# Controler_3_5.net
KiCad netlist of a schematic drawn in EAGLE
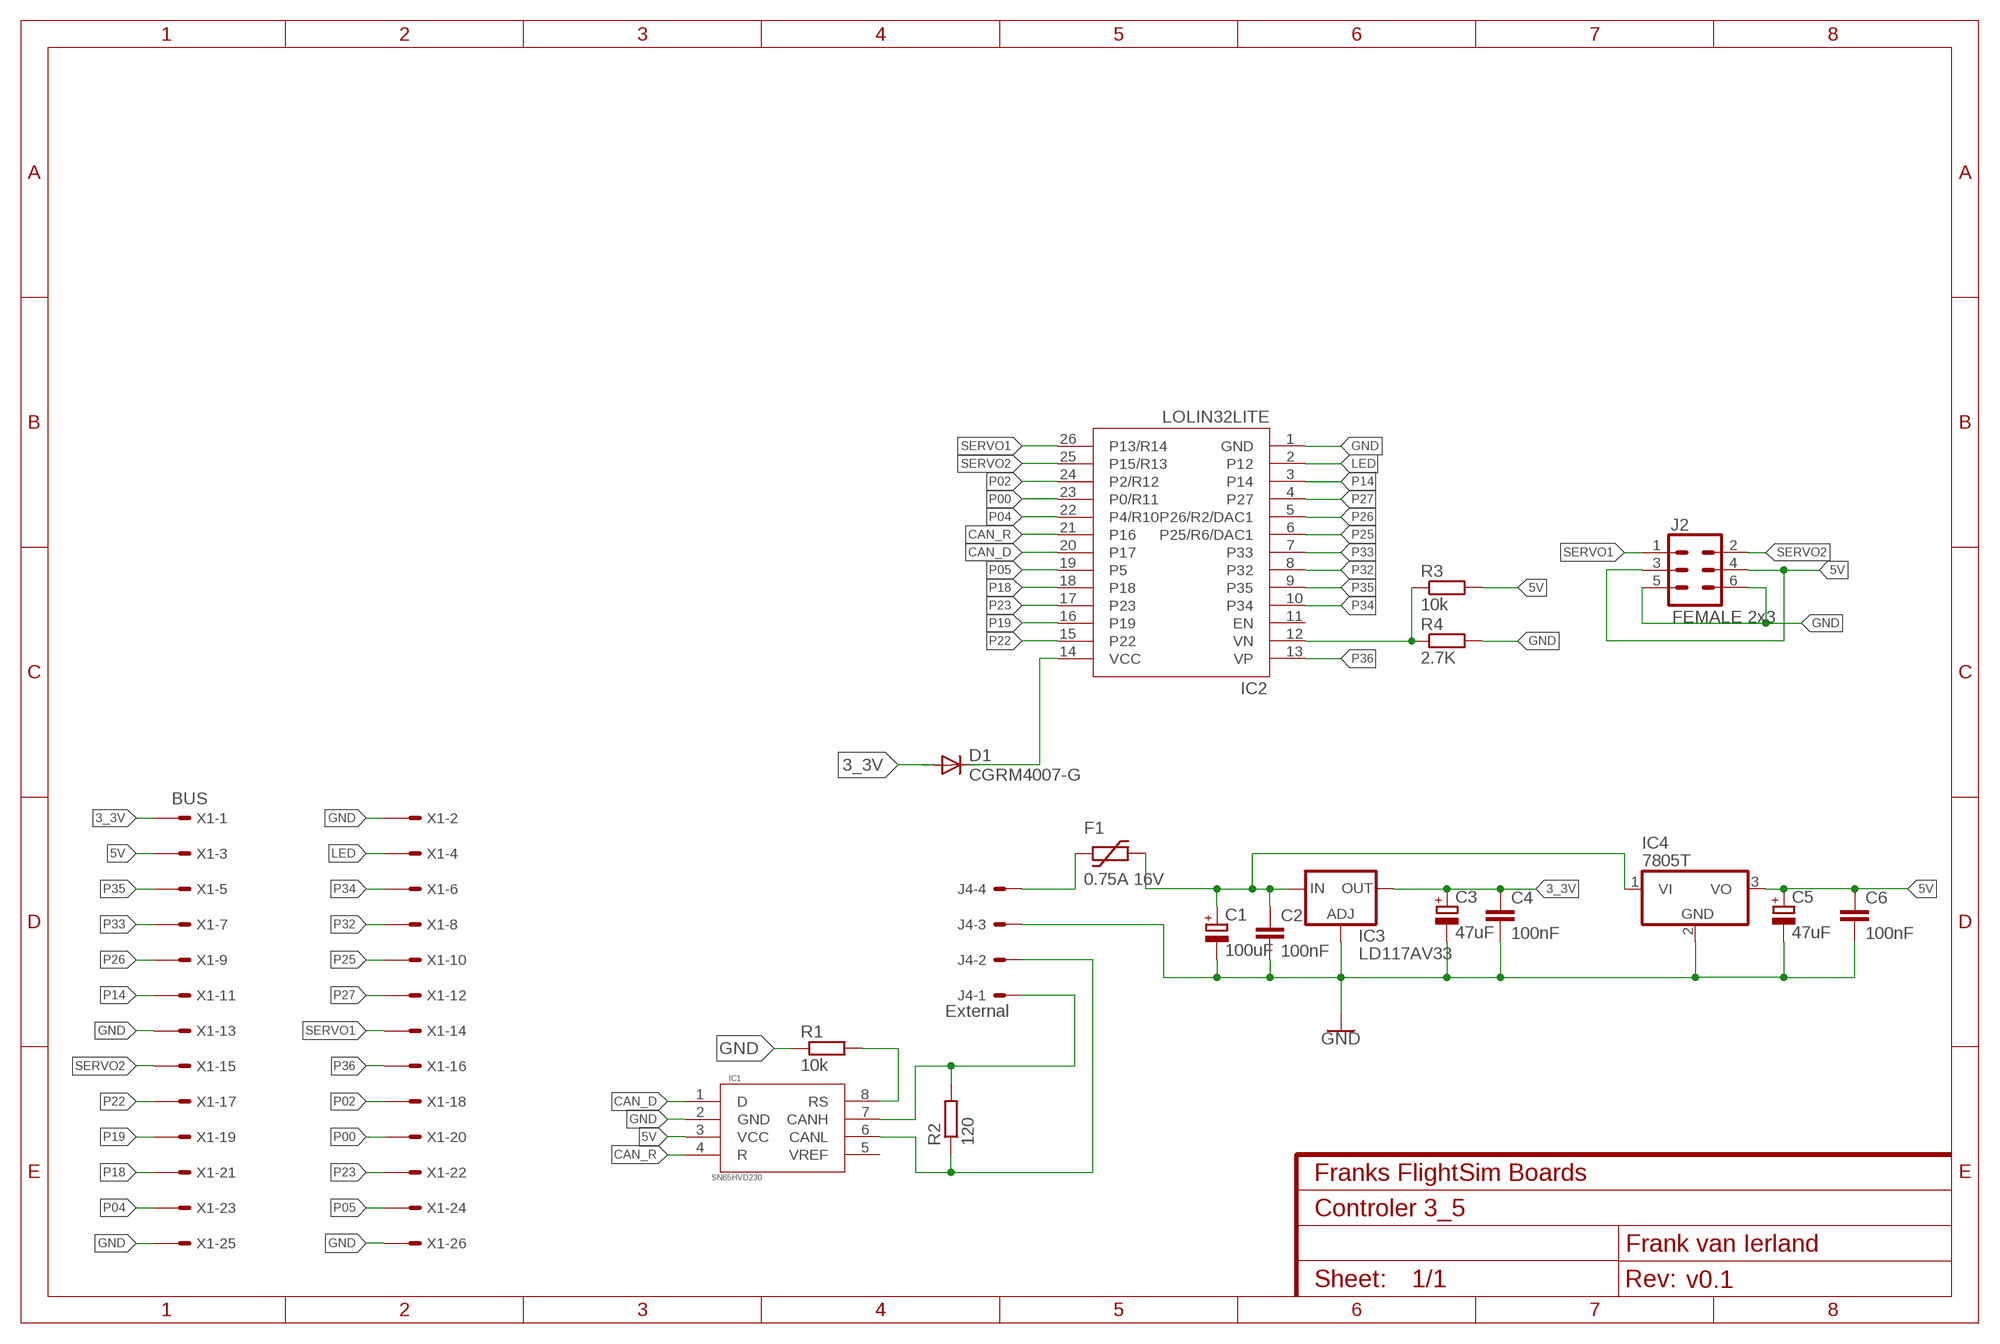
[diagram p0: schematic, sheet 1]

(export (version "E")
  (design (tool "Eeschema 10.0.6"))
  (components
    (comp (ref "C1")
      (value "100uF")
      (footprint "eagle-import:153CLV-0505")
      (libsource (lib "eagle-import") (part "CPOL-EU153CLV-0505"))
    )
    (comp (ref "C2")
      (value "100nF")
      (footprint "eagle-import:C0805")
      (libsource (lib "eagle-import") (part "C-EUC0805"))
    )
    (comp (ref "C3")
      (value "47uF")
      (footprint "eagle-import:CT3528")
      (libsource (lib "eagle-import") (part "CPOL-EUCT3528"))
    )
    (comp (ref "C4")
      (value "100nF")
      (footprint "eagle-import:C0805")
      (libsource (lib "eagle-import") (part "C-EUC0805"))
    )
    (comp (ref "C5")
      (value "47uF")
      (footprint "eagle-import:CT3528")
      (libsource (lib "eagle-import") (part "CPOL-EUCT3528"))
    )
    (comp (ref "C6")
      (value "100nF")
      (footprint "eagle-import:C0805")
      (libsource (lib "eagle-import") (part "C-EUC0805"))
    )
    (comp (ref "D1")
      (value "CGRM4007-G")
      (footprint "eagle-import:SOD-123_MINI-SMA")
      (libsource (lib "eagle-import") (part "CGRM400-G7"))
    )
    (comp (ref "F1")
      (value "0.75A 16V")
      (footprint "eagle-import:1812L")
      (libsource (lib "eagle-import") (part "1812L"))
    )
    (comp (ref "IC1")
      (value "SN65HVD230")
      (footprint "eagle-import:SO08")
      (libsource (lib "eagle-import") (part "SN65HVD230"))
    )
    (comp (ref "IC2")
      (value "LOLIN32LITE")
      (footprint "eagle-import:LOLIN32LITE")
      (libsource (lib "eagle-import") (part "LOLIN32LITE"))
    )
    (comp (ref "IC3")
      (value "LD117AV33")
      (footprint "eagle-import:TO220L1")
      (libsource (lib "eagle-import") (part "LD117A?V33"))
    )
    (comp (ref "IC4")
      (value "7805T")
      (footprint "eagle-import:TO220H")
      (libsource (lib "eagle-import") (part "78T05"))
    )
    (comp (ref "J2")
      (value "FEMALE 2x3")
      (footprint "eagle-import:2X3")
      (libsource (lib "eagle-import") (part "CONN_03X2FEMALE"))
    )
    (comp (ref "J4")
      (value "External")
      (footprint "eagle-import:6410-04")
      (fields (field (name "MF") "MOLEX"))
      (libsource (lib "eagle-import") (part "22-?-0427-2041"))
    )
    (comp (ref "R1")
      (value "10k")
      (footprint "eagle-import:M1206")
      (libsource (lib "eagle-import") (part "R-EU_M1206"))
    )
    (comp (ref "R2")
      (value "120")
      (footprint "eagle-import:R1210")
      (libsource (lib "eagle-import") (part "R-EU_R1210"))
    )
    (comp (ref "R3")
      (value "10k")
      (footprint "eagle-import:M1206")
      (libsource (lib "eagle-import") (part "R-EU_M1206"))
    )
    (comp (ref "R4")
      (value "2.7K")
      (footprint "eagle-import:M1206")
      (libsource (lib "eagle-import") (part "R-EU_M1206"))
    )
    (comp (ref "X1")
      (value "BUS")
      (footprint "eagle-import:057-026-1")
      (libsource (lib "eagle-import") (part "057-026-1"))
    )
  )
  (nets
    (net (code "1") (name "3_3V") (class "Default")
      (node (ref "C3") (pin "+") (pinfunction "+_+") (pintype "passive"))
      (node (ref "C4") (pin "1") (pinfunction "1_1") (pintype "passive"))
      (node (ref "D1") (pin "A") (pinfunction "A_A") (pintype "passive"))
      (node (ref "IC3") (pin "2") (pinfunction "OUT_2") (pintype "passive"))
      (node (ref "X1") (pin "1") (pinfunction "S_1") (pintype "passive"))
    )
    (net (code "2") (name "5V") (class "Default")
      (node (ref "C5") (pin "+") (pinfunction "+_+") (pintype "passive"))
      (node (ref "C6") (pin "1") (pinfunction "1_1") (pintype "passive"))
      (node (ref "IC1") (pin "3") (pinfunction "VCC_3") (pintype "bidirectional"))
      (node (ref "IC4") (pin "3") (pinfunction "VO_3") (pintype "passive"))
      (node (ref "J2") (pin "3") (pinfunction "3_3") (pintype "bidirectional"))
      (node (ref "J2") (pin "4") (pinfunction "4_4") (pintype "bidirectional"))
      (node (ref "R3") (pin "2") (pinfunction "2_2") (pintype "passive"))
      (node (ref "X1") (pin "3") (pinfunction "S_3") (pintype "passive"))
    )
    (net (code "3") (name "CAN_D") (class "Default")
      (node (ref "IC1") (pin "1") (pinfunction "D_1") (pintype "bidirectional"))
      (node (ref "IC2") (pin "20") (pinfunction "P17_20") (pintype "bidirectional"))
    )
    (net (code "4") (name "CAN_R") (class "Default")
      (node (ref "IC1") (pin "4") (pinfunction "R_4") (pintype "bidirectional"))
      (node (ref "IC2") (pin "21") (pinfunction "P16_21") (pintype "bidirectional"))
    )
    (net (code "5") (name "GND") (class "Default")
      (node (ref "C1") (pin "-") (pinfunction "-_-") (pintype "passive"))
      (node (ref "C2") (pin "2") (pinfunction "2_2") (pintype "passive"))
      (node (ref "C3") (pin "-") (pinfunction "-_-") (pintype "passive"))
      (node (ref "C4") (pin "2") (pinfunction "2_2") (pintype "passive"))
      (node (ref "C5") (pin "-") (pinfunction "-_-") (pintype "passive"))
      (node (ref "C6") (pin "2") (pinfunction "2_2") (pintype "passive"))
      (node (ref "IC1") (pin "2") (pinfunction "GND_2") (pintype "bidirectional"))
      (node (ref "IC2") (pin "1") (pinfunction "GND_1") (pintype "power_in"))
      (node (ref "IC3") (pin "1") (pinfunction "ADJ_1") (pintype "input"))
      (node (ref "IC4") (pin "2") (pinfunction "GND_2") (pintype "passive"))
      (node (ref "J2") (pin "5") (pinfunction "5_5") (pintype "bidirectional"))
      (node (ref "J2") (pin "6") (pinfunction "6_6") (pintype "bidirectional"))
      (node (ref "J4") (pin "3") (pinfunction "S_3") (pintype "passive"))
      (node (ref "R1") (pin "1") (pinfunction "1_1") (pintype "passive"))
      (node (ref "R4") (pin "2") (pinfunction "2_2") (pintype "passive"))
      (node (ref "X1") (pin "13") (pinfunction "S_13") (pintype "passive"))
      (node (ref "X1") (pin "2") (pinfunction "S_2") (pintype "passive"))
      (node (ref "X1") (pin "25") (pinfunction "S_25") (pintype "passive"))
      (node (ref "X1") (pin "26") (pinfunction "S_26") (pintype "passive"))
    )
    (net (code "6") (name "LED") (class "Default")
      (node (ref "IC2") (pin "2") (pinfunction "P12_2") (pintype "bidirectional"))
      (node (ref "X1") (pin "4") (pinfunction "S_4") (pintype "passive"))
    )
    (net (code "7") (name "Net-(IC1-CANH)") (class "Default")
      (node (ref "IC1") (pin "7") (pinfunction "CANH_7") (pintype "bidirectional"))
      (node (ref "J4") (pin "1") (pinfunction "S_1") (pintype "passive"))
      (node (ref "R2") (pin "2") (pinfunction "2_2") (pintype "passive"))
    )
    (net (code "8") (name "Net-(IC1-CANL)") (class "Default")
      (node (ref "IC1") (pin "6") (pinfunction "CANL_6") (pintype "bidirectional"))
      (node (ref "J4") (pin "2") (pinfunction "S_2") (pintype "passive"))
      (node (ref "R2") (pin "1") (pinfunction "1_1") (pintype "passive"))
    )
    (net (code "9") (name "Net-(IC1-RS)") (class "Default")
      (node (ref "IC1") (pin "8") (pinfunction "RS_8") (pintype "bidirectional"))
      (node (ref "R1") (pin "2") (pinfunction "2_2") (pintype "passive"))
    )
    (net (code "10") (name "Net-(IC2-VCC)") (class "Default")
      (node (ref "D1") (pin "C") (pinfunction "C_C") (pintype "passive"))
      (node (ref "IC2") (pin "14") (pinfunction "VCC_14") (pintype "power_in"))
    )
    (net (code "11") (name "Net-(IC2-VN)") (class "Default")
      (node (ref "IC2") (pin "12") (pinfunction "VN_12") (pintype "bidirectional"))
      (node (ref "R3") (pin "1") (pinfunction "1_1") (pintype "passive"))
      (node (ref "R4") (pin "1") (pinfunction "1_1") (pintype "passive"))
    )
    (net (code "12") (name "Net-(IC3-IN)") (class "Default")
      (node (ref "C1") (pin "+") (pinfunction "+_+") (pintype "passive"))
      (node (ref "C2") (pin "1") (pinfunction "1_1") (pintype "passive"))
      (node (ref "F1") (pin "2") (pinfunction "2_2") (pintype "passive"))
      (node (ref "IC3") (pin "3") (pinfunction "IN_3") (pintype "input"))
      (node (ref "IC4") (pin "1") (pinfunction "VI_1") (pintype "input"))
    )
    (net (code "13") (name "Net-(J4D-S)") (class "Default")
      (node (ref "F1") (pin "1") (pinfunction "1_1") (pintype "passive"))
      (node (ref "J4") (pin "4") (pinfunction "S_4") (pintype "passive"))
    )
    (net (code "14") (name "P00") (class "Default")
      (node (ref "IC2") (pin "23") (pinfunction "P0/R11_23") (pintype "bidirectional"))
      (node (ref "X1") (pin "20") (pinfunction "S_20") (pintype "passive"))
    )
    (net (code "15") (name "P02") (class "Default")
      (node (ref "IC2") (pin "24") (pinfunction "P2/R12_24") (pintype "bidirectional"))
      (node (ref "X1") (pin "18") (pinfunction "S_18") (pintype "passive"))
    )
    (net (code "16") (name "P04") (class "Default")
      (node (ref "IC2") (pin "22") (pinfunction "P4/R10_22") (pintype "bidirectional"))
      (node (ref "X1") (pin "23") (pinfunction "S_23") (pintype "passive"))
    )
    (net (code "17") (name "P05") (class "Default")
      (node (ref "IC2") (pin "19") (pinfunction "P5_19") (pintype "bidirectional"))
      (node (ref "X1") (pin "24") (pinfunction "S_24") (pintype "passive"))
    )
    (net (code "18") (name "P14") (class "Default")
      (node (ref "IC2") (pin "3") (pinfunction "P14_3") (pintype "bidirectional"))
      (node (ref "X1") (pin "11") (pinfunction "S_11") (pintype "passive"))
    )
    (net (code "19") (name "P18") (class "Default")
      (node (ref "IC2") (pin "18") (pinfunction "P18_18") (pintype "bidirectional"))
      (node (ref "X1") (pin "21") (pinfunction "S_21") (pintype "passive"))
    )
    (net (code "20") (name "P19") (class "Default")
      (node (ref "IC2") (pin "16") (pinfunction "P19_16") (pintype "bidirectional"))
      (node (ref "X1") (pin "19") (pinfunction "S_19") (pintype "passive"))
    )
    (net (code "21") (name "P22") (class "Default")
      (node (ref "IC2") (pin "15") (pinfunction "P22_15") (pintype "bidirectional"))
      (node (ref "X1") (pin "17") (pinfunction "S_17") (pintype "passive"))
    )
    (net (code "22") (name "P23") (class "Default")
      (node (ref "IC2") (pin "17") (pinfunction "P23_17") (pintype "bidirectional"))
      (node (ref "X1") (pin "22") (pinfunction "S_22") (pintype "passive"))
    )
    (net (code "23") (name "P25") (class "Default")
      (node (ref "IC2") (pin "6") (pinfunction "P25/R6/DAC1_6") (pintype "bidirectional"))
      (node (ref "X1") (pin "10") (pinfunction "S_10") (pintype "passive"))
    )
    (net (code "24") (name "P26") (class "Default")
      (node (ref "IC2") (pin "5") (pinfunction "P26/R2/DAC1_5") (pintype "bidirectional"))
      (node (ref "X1") (pin "9") (pinfunction "S_9") (pintype "passive"))
    )
    (net (code "25") (name "P27") (class "Default")
      (node (ref "IC2") (pin "4") (pinfunction "P27_4") (pintype "bidirectional"))
      (node (ref "X1") (pin "12") (pinfunction "S_12") (pintype "passive"))
    )
    (net (code "26") (name "P32") (class "Default")
      (node (ref "IC2") (pin "8") (pinfunction "P32_8") (pintype "bidirectional"))
      (node (ref "X1") (pin "8") (pinfunction "S_8") (pintype "passive"))
    )
    (net (code "27") (name "P33") (class "Default")
      (node (ref "IC2") (pin "7") (pinfunction "P33_7") (pintype "bidirectional"))
      (node (ref "X1") (pin "7") (pinfunction "S_7") (pintype "passive"))
    )
    (net (code "28") (name "P34") (class "Default")
      (node (ref "IC2") (pin "10") (pinfunction "P34_10") (pintype "bidirectional"))
      (node (ref "X1") (pin "6") (pinfunction "S_6") (pintype "passive"))
    )
    (net (code "29") (name "P35") (class "Default")
      (node (ref "IC2") (pin "9") (pinfunction "P35_9") (pintype "bidirectional"))
      (node (ref "X1") (pin "5") (pinfunction "S_5") (pintype "passive"))
    )
    (net (code "30") (name "P36") (class "Default")
      (node (ref "IC2") (pin "13") (pinfunction "VP_13") (pintype "bidirectional"))
      (node (ref "X1") (pin "16") (pinfunction "S_16") (pintype "passive"))
    )
    (net (code "31") (name "SERVO1") (class "Default")
      (node (ref "IC2") (pin "26") (pinfunction "P13/R14_26") (pintype "bidirectional"))
      (node (ref "J2") (pin "1") (pinfunction "1_1") (pintype "bidirectional"))
      (node (ref "X1") (pin "14") (pinfunction "S_14") (pintype "passive"))
    )
    (net (code "32") (name "SERVO2") (class "Default")
      (node (ref "IC2") (pin "25") (pinfunction "P15/R13_25") (pintype "bidirectional"))
      (node (ref "J2") (pin "2") (pinfunction "2_2") (pintype "bidirectional"))
      (node (ref "X1") (pin "15") (pinfunction "S_15") (pintype "passive"))
    )
    (net (code "33") (name "unconnected-(IC1-VREF-Pad5)") (class "Default")
      (node (ref "IC1") (pin "5") (pinfunction "VREF_5") (pintype "bidirectional"))
    )
    (net (code "34") (name "unconnected-(IC2-EN-Pad11)") (class "Default")
      (node (ref "IC2") (pin "11") (pinfunction "EN_11") (pintype "bidirectional"))
    )
  )
)
